# A4950.net
KiCad netlist of a schematic drawn in Altium Designer
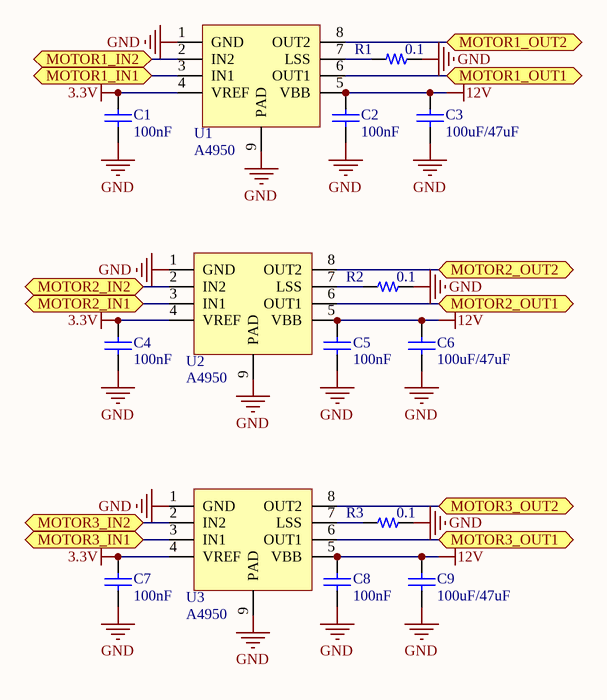
[diagram p0: A4950.SchDoc]

(export (version "E")
  (design (tool "Eeschema 10.0.6"))
  (components
    (comp (ref "C1")
      (value "100nF")
      (footprint "dq - 0402")
      (description "Capacitor")
      (fields (field (name "Comment") "Cap") (field (name "PUBLISHER") "Altium Limited"))
      (libsource (lib "weifengdq") (part "DQ_Cap"))
    )
    (comp (ref "C2")
      (value "100nF")
      (footprint "dq - 0402")
      (description "Capacitor")
      (fields (field (name "Comment") "Cap") (field (name "PUBLISHER") "Altium Limited"))
      (libsource (lib "weifengdq") (part "DQ_Cap"))
    )
    (comp (ref "C3")
      (value "100uF/47uF")
      (footprint "dq - 1210")
      (description "Capacitor")
      (fields (field (name "Comment") "Cap") (field (name "PUBLISHER") "Altium Limited"))
      (libsource (lib "weifengdq") (part "DQ_Cap"))
    )
    (comp (ref "C4")
      (value "100nF")
      (footprint "dq - 0402")
      (description "Capacitor")
      (fields (field (name "Comment") "Cap") (field (name "PUBLISHER") "Altium Limited"))
      (libsource (lib "weifengdq") (part "DQ_Cap"))
    )
    (comp (ref "C5")
      (value "100nF")
      (footprint "dq - 0402")
      (description "Capacitor")
      (fields (field (name "Comment") "Cap") (field (name "PUBLISHER") "Altium Limited"))
      (libsource (lib "weifengdq") (part "DQ_Cap"))
    )
    (comp (ref "C6")
      (value "100uF/47uF")
      (footprint "dq - 1210")
      (description "Capacitor")
      (fields (field (name "Comment") "Cap") (field (name "PUBLISHER") "Altium Limited"))
      (libsource (lib "weifengdq") (part "DQ_Cap"))
    )
    (comp (ref "C7")
      (value "100nF")
      (footprint "dq - 0402")
      (description "Capacitor")
      (fields (field (name "Comment") "Cap") (field (name "PUBLISHER") "Altium Limited"))
      (libsource (lib "weifengdq") (part "DQ_Cap"))
    )
    (comp (ref "C8")
      (value "100nF")
      (footprint "dq - 0402")
      (description "Capacitor")
      (fields (field (name "Comment") "Cap") (field (name "PUBLISHER") "Altium Limited"))
      (libsource (lib "weifengdq") (part "DQ_Cap"))
    )
    (comp (ref "C9")
      (value "100uF/47uF")
      (footprint "dq - 1210")
      (description "Capacitor")
      (fields (field (name "Comment") "Cap") (field (name "PUBLISHER") "Altium Limited"))
      (libsource (lib "weifengdq") (part "DQ_Cap"))
    )
    (comp (ref "R1")
      (value "0.1")
      (footprint "DQ - 2512")
      (description "Resistance")
      (fields (field (name "Comment") "Res"))
      (libsource (lib "weifengdq") (part "DQ_Res"))
    )
    (comp (ref "R2")
      (value "0.1")
      (footprint "DQ - 2512")
      (description "Resistance")
      (fields (field (name "Comment") "Res"))
      (libsource (lib "weifengdq") (part "DQ_Res"))
    )
    (comp (ref "R3")
      (value "0.1")
      (footprint "DQ - 2512")
      (description "Resistance")
      (fields (field (name "Comment") "Res"))
      (libsource (lib "weifengdq") (part "DQ_Res"))
    )
    (comp (ref "U1")
      (value "A4950")
      (footprint "LC-SOIC-8_150mil")
      (libsource (lib "weifengdq") (part "A4950"))
    )
    (comp (ref "U2")
      (value "A4950")
      (footprint "LC-SOIC-8_150mil")
      (libsource (lib "weifengdq") (part "A4950"))
    )
    (comp (ref "U3")
      (value "A4950")
      (footprint "LC-SOIC-8_150mil")
      (libsource (lib "weifengdq") (part "A4950"))
    )
  )
  (nets
    (net (code "1") (name "/MOTOR1_IN1") (class "Default")
      (node (ref "U1") (pin "3") (pinfunction "IN1_3") (pintype "passive"))
    )
    (net (code "2") (name "/MOTOR1_IN2") (class "Default")
      (node (ref "U1") (pin "2") (pinfunction "IN2_2") (pintype "passive"))
    )
    (net (code "3") (name "/MOTOR1_OUT1") (class "Default")
      (node (ref "U1") (pin "6") (pinfunction "OUT1_6") (pintype "passive"))
    )
    (net (code "4") (name "/MOTOR1_OUT2") (class "Default")
      (node (ref "U1") (pin "8") (pinfunction "OUT2_8") (pintype "passive"))
    )
    (net (code "5") (name "/MOTOR2_IN1") (class "Default")
      (node (ref "U2") (pin "3") (pinfunction "IN1_3") (pintype "passive"))
    )
    (net (code "6") (name "/MOTOR2_IN2") (class "Default")
      (node (ref "U2") (pin "2") (pinfunction "IN2_2") (pintype "passive"))
    )
    (net (code "7") (name "/MOTOR2_OUT1") (class "Default")
      (node (ref "U2") (pin "6") (pinfunction "OUT1_6") (pintype "passive"))
    )
    (net (code "8") (name "/MOTOR2_OUT2") (class "Default")
      (node (ref "U2") (pin "8") (pinfunction "OUT2_8") (pintype "passive"))
    )
    (net (code "9") (name "/MOTOR3_IN1") (class "Default")
      (node (ref "U3") (pin "3") (pinfunction "IN1_3") (pintype "passive"))
    )
    (net (code "10") (name "/MOTOR3_IN2") (class "Default")
      (node (ref "U3") (pin "2") (pinfunction "IN2_2") (pintype "passive"))
    )
    (net (code "11") (name "/MOTOR3_OUT1") (class "Default")
      (node (ref "U3") (pin "6") (pinfunction "OUT1_6") (pintype "passive"))
    )
    (net (code "12") (name "/MOTOR3_OUT2") (class "Default")
      (node (ref "U3") (pin "8") (pinfunction "OUT2_8") (pintype "passive"))
    )
    (net (code "13") (name "3.3V") (class "Default")
      (node (ref "C1") (pin "2") (pinfunction "2_2") (pintype "passive"))
      (node (ref "C4") (pin "2") (pinfunction "2_2") (pintype "passive"))
      (node (ref "C7") (pin "2") (pinfunction "2_2") (pintype "passive"))
      (node (ref "U1") (pin "4") (pinfunction "VREF_4") (pintype "passive"))
      (node (ref "U2") (pin "4") (pinfunction "VREF_4") (pintype "passive"))
      (node (ref "U3") (pin "4") (pinfunction "VREF_4") (pintype "passive"))
    )
    (net (code "14") (name "12V") (class "Default")
      (node (ref "C2") (pin "2") (pinfunction "2_2") (pintype "passive"))
      (node (ref "C3") (pin "2") (pinfunction "2_2") (pintype "passive"))
      (node (ref "C5") (pin "2") (pinfunction "2_2") (pintype "passive"))
      (node (ref "C6") (pin "2") (pinfunction "2_2") (pintype "passive"))
      (node (ref "C8") (pin "2") (pinfunction "2_2") (pintype "passive"))
      (node (ref "C9") (pin "2") (pinfunction "2_2") (pintype "passive"))
      (node (ref "U1") (pin "5") (pinfunction "VBB_5") (pintype "passive"))
      (node (ref "U2") (pin "5") (pinfunction "VBB_5") (pintype "passive"))
      (node (ref "U3") (pin "5") (pinfunction "VBB_5") (pintype "passive"))
    )
    (net (code "15") (name "GND") (class "Default")
      (node (ref "C1") (pin "1") (pinfunction "1_1") (pintype "passive"))
      (node (ref "C2") (pin "1") (pinfunction "1_1") (pintype "passive"))
      (node (ref "C3") (pin "1") (pinfunction "1_1") (pintype "passive"))
      (node (ref "C4") (pin "1") (pinfunction "1_1") (pintype "passive"))
      (node (ref "C5") (pin "1") (pinfunction "1_1") (pintype "passive"))
      (node (ref "C6") (pin "1") (pinfunction "1_1") (pintype "passive"))
      (node (ref "C7") (pin "1") (pinfunction "1_1") (pintype "passive"))
      (node (ref "C8") (pin "1") (pinfunction "1_1") (pintype "passive"))
      (node (ref "C9") (pin "1") (pinfunction "1_1") (pintype "passive"))
      (node (ref "R1") (pin "1") (pintype "passive"))
      (node (ref "R2") (pin "1") (pintype "passive"))
      (node (ref "R3") (pin "1") (pintype "passive"))
      (node (ref "U1") (pin "1") (pinfunction "GND_1") (pintype "passive"))
      (node (ref "U1") (pin "9") (pinfunction "PAD_9") (pintype "passive"))
      (node (ref "U2") (pin "1") (pinfunction "GND_1") (pintype "passive"))
      (node (ref "U2") (pin "9") (pinfunction "PAD_9") (pintype "passive"))
      (node (ref "U3") (pin "1") (pinfunction "GND_1") (pintype "passive"))
      (node (ref "U3") (pin "9") (pinfunction "PAD_9") (pintype "passive"))
    )
    (net (code "16") (name "Net-(U1-LSS)") (class "Default")
      (node (ref "R1") (pin "2") (pintype "passive"))
      (node (ref "U1") (pin "7") (pinfunction "LSS_7") (pintype "passive"))
    )
    (net (code "17") (name "Net-(U2-LSS)") (class "Default")
      (node (ref "R2") (pin "2") (pintype "passive"))
      (node (ref "U2") (pin "7") (pinfunction "LSS_7") (pintype "passive"))
    )
    (net (code "18") (name "Net-(U3-LSS)") (class "Default")
      (node (ref "R3") (pin "2") (pintype "passive"))
      (node (ref "U3") (pin "7") (pinfunction "LSS_7") (pintype "passive"))
    )
  )
)
